# 13-Fusing.net
KiCad netlist of a schematic drawn in Altium Designer
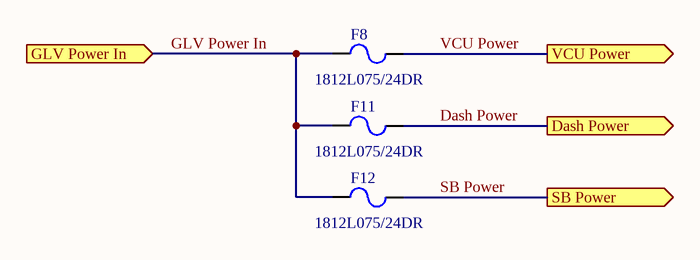
[diagram p0: 13-Fusing.SchDoc]

(export (version "E")
  (design (tool "Eeschema 10.0.6"))
  (components
    (comp (ref "F8")
      (value "1812L075/24DR")
      (footprint "LFUS-1812L07524DR_V")
      (description "Poly-Fuse(R) Resettable PTC, 24 V, 100 A, -40 to 85 degC, 2-Pin SMD, RoHS, Tape and Reel")
      (fields (field (name "MANUFACTURER") "Littelfuse"))
      (libsource (lib "Altium Content Vault") (part "FUSE-2"))
    )
    (comp (ref "F11")
      (value "1812L075/24DR")
      (footprint "LFUS-1812L07524DR_V")
      (description "Poly-Fuse(R) Resettable PTC, 24 V, 100 A, -40 to 85 degC, 2-Pin SMD, RoHS, Tape and Reel")
      (fields (field (name "MANUFACTURER") "Littelfuse"))
      (libsource (lib "Altium Content Vault") (part "FUSE-2"))
    )
    (comp (ref "F12")
      (value "1812L075/24DR")
      (footprint "LFUS-1812L07524DR_V")
      (description "Poly-Fuse(R) Resettable PTC, 24 V, 100 A, -40 to 85 degC, 2-Pin SMD, RoHS, Tape and Reel")
      (fields (field (name "MANUFACTURER") "Littelfuse"))
      (libsource (lib "Altium Content Vault") (part "FUSE-2"))
    )
  )
  (nets
    (net (code "1") (name "/Dash Power") (class "Default")
      (node (ref "F11") (pin "2") (pinfunction "2_2") (pintype "passive"))
    )
    (net (code "2") (name "/GLV Power In") (class "Default")
      (node (ref "F11") (pin "1") (pinfunction "1_1") (pintype "passive"))
      (node (ref "F12") (pin "1") (pinfunction "1_1") (pintype "passive"))
      (node (ref "F8") (pin "1") (pinfunction "1_1") (pintype "passive"))
    )
    (net (code "3") (name "/SB Power") (class "Default")
      (node (ref "F12") (pin "2") (pinfunction "2_2") (pintype "passive"))
    )
    (net (code "4") (name "/VCU Power") (class "Default")
      (node (ref "F8") (pin "2") (pinfunction "2_2") (pintype "passive"))
    )
  )
)
